# design.net
KiCad netlist of a schematic drawn in Altium Designer
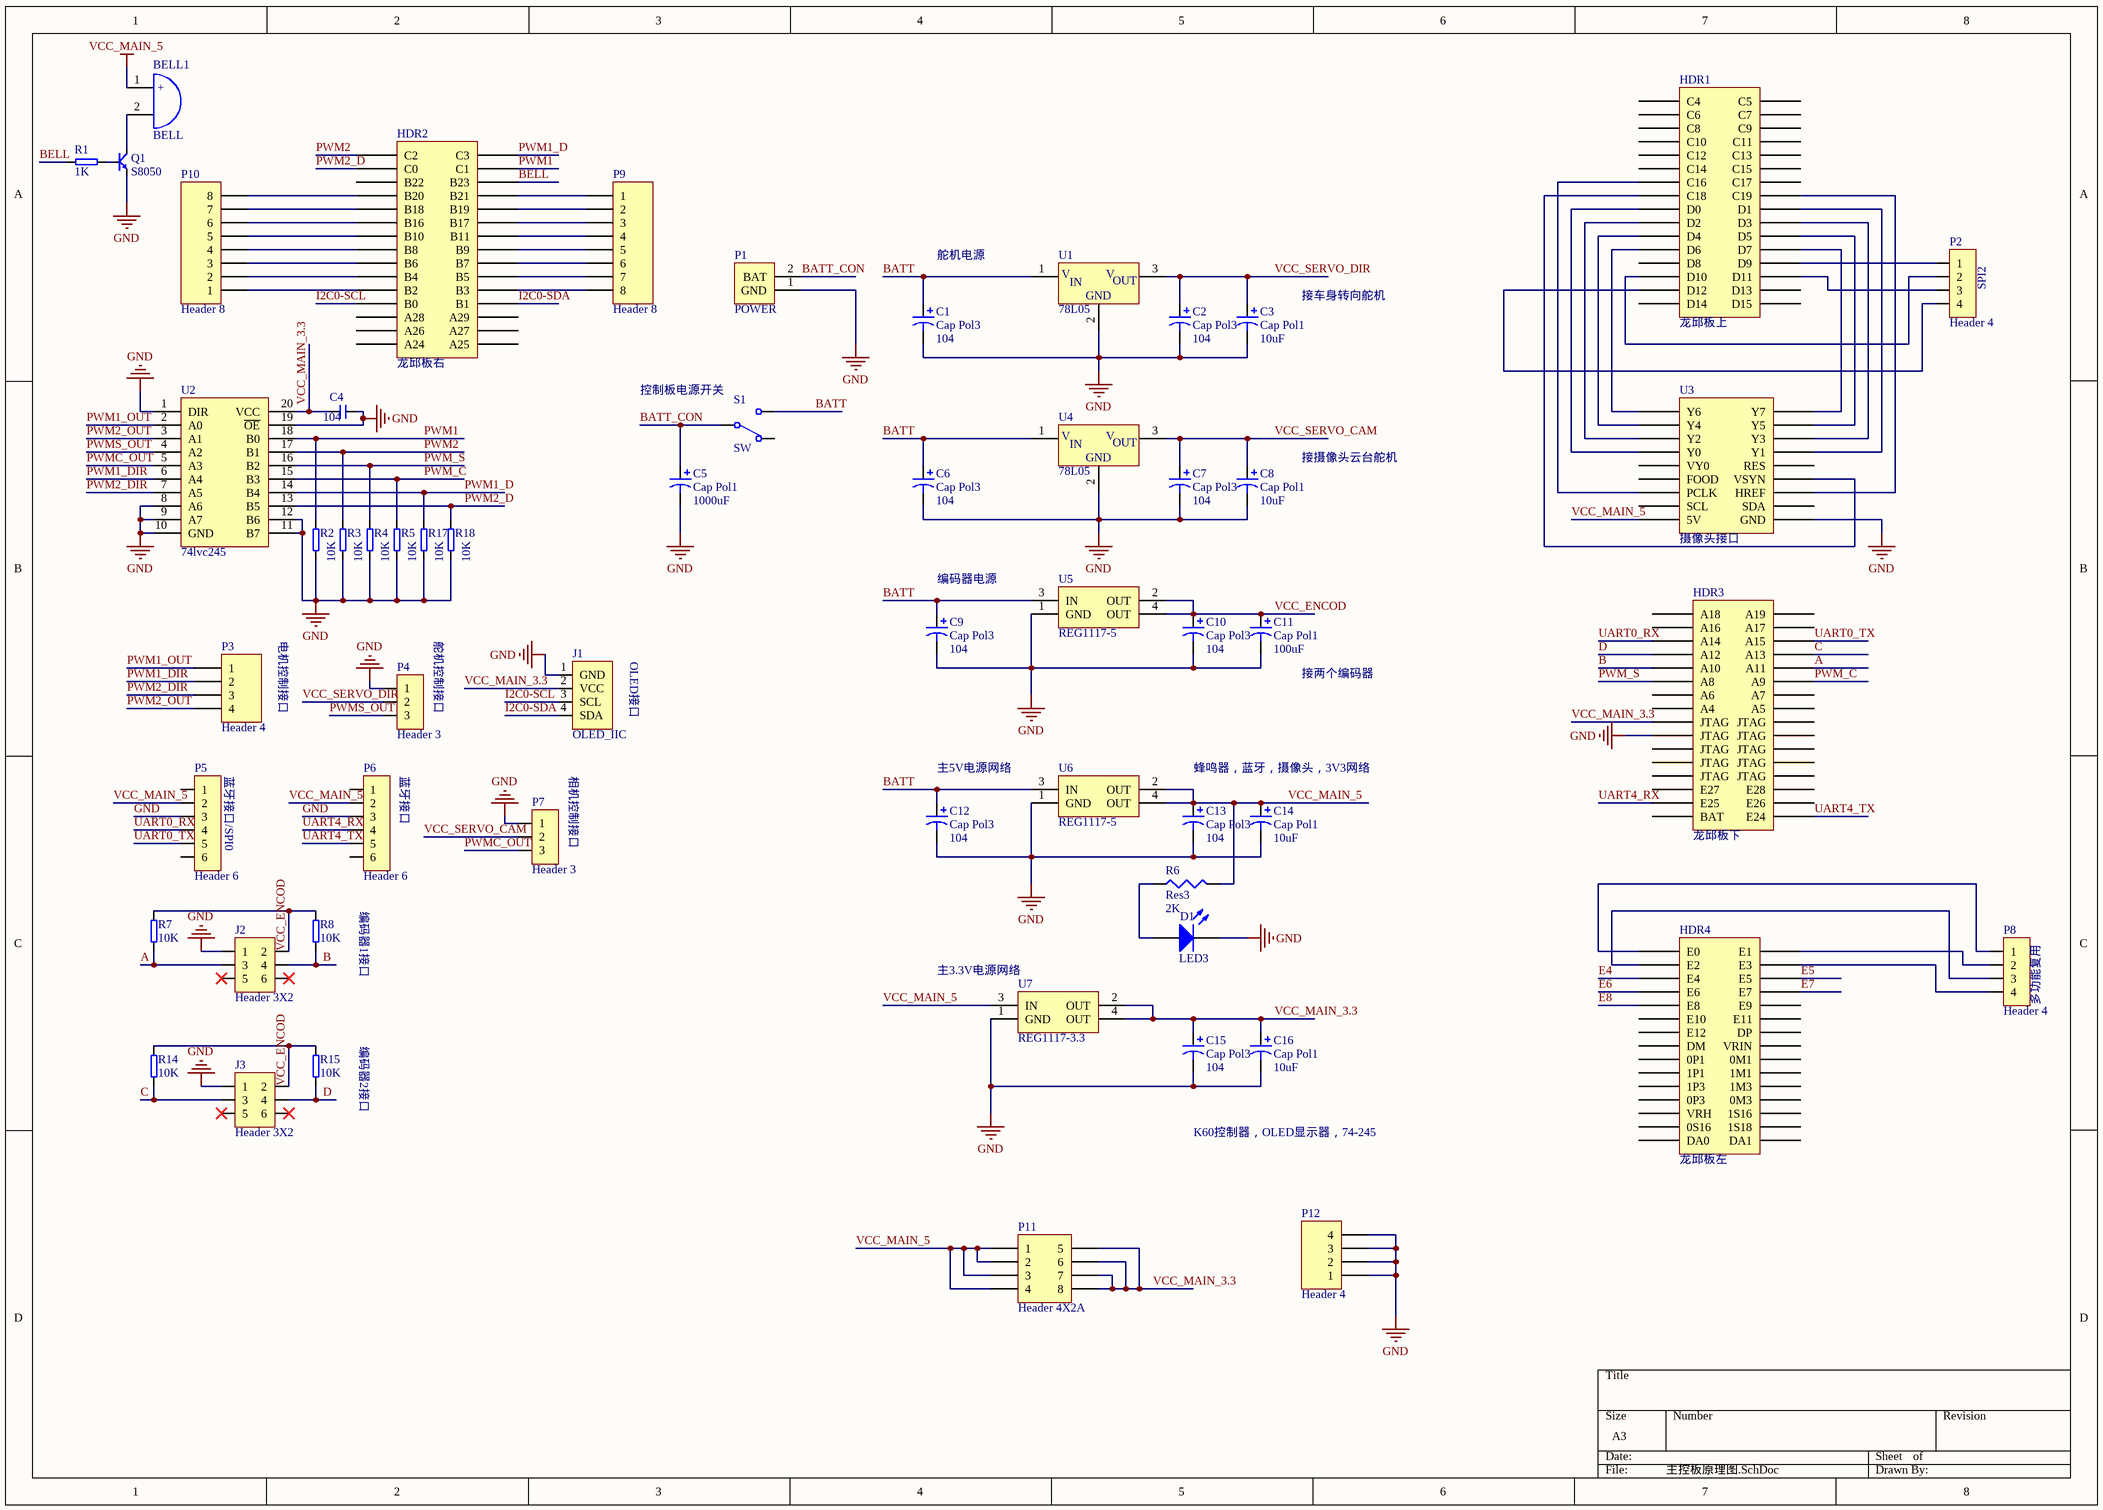
[diagram p0: 主控板原理图.SchDoc]

(export (version "E")
  (design (tool "Eeschema 10.0.6"))
  (components
    (comp (ref "BELL1")
      (value "BELL")
      (footprint "BUZZER")
      (libsource (lib "2017elec_Library") (part "BELL"))
    )
    (comp (ref "C1")
      (value "Cap Pol3")
      (footprint "C0805")
      (description "Polarized Capacitor (Surface Mount)")
      (fields (field (name "ALTIUM_VALUE") "104") (field (name "PUBLISHER") "Altium Limited"))
      (libsource (lib "Miscellaneous Devices") (part "Cap Pol3"))
    )
    (comp (ref "C2")
      (value "Cap Pol3")
      (footprint "C0805")
      (description "Polarized Capacitor (Surface Mount)")
      (fields (field (name "ALTIUM_VALUE") "104") (field (name "PUBLISHER") "Altium Limited"))
      (libsource (lib "Miscellaneous Devices") (part "Cap Pol3"))
    )
    (comp (ref "C3")
      (value "Cap Pol1")
      (footprint "3216-CAP-TA")
      (description "Polarized Capacitor (Radial)")
      (fields (field (name "ALTIUM_VALUE") "10uF") (field (name "PUBLISHER") "Altium Limited"))
      (libsource (lib "Miscellaneous Devices") (part "Cap Pol1"))
    )
    (comp (ref "C4")
      (value "104")
      (footprint "0603-CAP")
      (libsource (lib "2017elec_Library") (part "CAP_0603"))
    )
    (comp (ref "C5")
      (value "Cap Pol1")
      (footprint "CAPP")
      (description "Polarized Capacitor (Radial)")
      (fields (field (name "ALTIUM_VALUE") "1000uF") (field (name "PUBLISHER") "Altium Limited"))
      (libsource (lib "Miscellaneous Devices") (part "Cap Pol1"))
    )
    (comp (ref "C6")
      (value "Cap Pol3")
      (footprint "C0805")
      (description "Polarized Capacitor (Surface Mount)")
      (fields (field (name "ALTIUM_VALUE") "104") (field (name "PUBLISHER") "Altium Limited"))
      (libsource (lib "Miscellaneous Devices") (part "Cap Pol3"))
    )
    (comp (ref "C7")
      (value "Cap Pol3")
      (footprint "C0805")
      (description "Polarized Capacitor (Surface Mount)")
      (fields (field (name "ALTIUM_VALUE") "104") (field (name "PUBLISHER") "Altium Limited"))
      (libsource (lib "Miscellaneous Devices") (part "Cap Pol3"))
    )
    (comp (ref "C8")
      (value "Cap Pol1")
      (footprint "3216-CAP-TA")
      (description "Polarized Capacitor (Radial)")
      (fields (field (name "ALTIUM_VALUE") "10uF") (field (name "PUBLISHER") "Altium Limited"))
      (libsource (lib "Miscellaneous Devices") (part "Cap Pol1"))
    )
    (comp (ref "C9")
      (value "Cap Pol3")
      (footprint "C0805")
      (description "Polarized Capacitor (Surface Mount)")
      (fields (field (name "ALTIUM_VALUE") "104") (field (name "PUBLISHER") "Altium Limited"))
      (libsource (lib "Miscellaneous Devices") (part "Cap Pol3"))
    )
    (comp (ref "C10")
      (value "Cap Pol3")
      (footprint "C0805")
      (description "Polarized Capacitor (Surface Mount)")
      (fields (field (name "ALTIUM_VALUE") "104") (field (name "PUBLISHER") "Altium Limited"))
      (libsource (lib "Miscellaneous Devices") (part "Cap Pol3"))
    )
    (comp (ref "C11")
      (value "Cap Pol1")
      (footprint "RB.1/.2")
      (description "Polarized Capacitor (Radial)")
      (fields (field (name "ALTIUM_VALUE") "100uF") (field (name "PUBLISHER") "Altium Limited"))
      (libsource (lib "Miscellaneous Devices") (part "Cap Pol1"))
    )
    (comp (ref "C12")
      (value "Cap Pol3")
      (footprint "C0805")
      (description "Polarized Capacitor (Surface Mount)")
      (fields (field (name "ALTIUM_VALUE") "104") (field (name "PUBLISHER") "Altium Limited"))
      (libsource (lib "Miscellaneous Devices") (part "Cap Pol3"))
    )
    (comp (ref "C13")
      (value "Cap Pol3")
      (footprint "C0805")
      (description "Polarized Capacitor (Surface Mount)")
      (fields (field (name "ALTIUM_VALUE") "104") (field (name "PUBLISHER") "Altium Limited"))
      (libsource (lib "Miscellaneous Devices") (part "Cap Pol3"))
    )
    (comp (ref "C14")
      (value "Cap Pol1")
      (footprint "3216-CAP-TA")
      (description "Polarized Capacitor (Radial)")
      (fields (field (name "ALTIUM_VALUE") "10uF") (field (name "PUBLISHER") "Altium Limited"))
      (libsource (lib "Miscellaneous Devices") (part "Cap Pol1"))
    )
    (comp (ref "C15")
      (value "Cap Pol3")
      (footprint "C0805")
      (description "Polarized Capacitor (Surface Mount)")
      (fields (field (name "ALTIUM_VALUE") "104") (field (name "PUBLISHER") "Altium Limited"))
      (libsource (lib "Miscellaneous Devices") (part "Cap Pol3"))
    )
    (comp (ref "C16")
      (value "Cap Pol1")
      (footprint "3216-CAP-TA")
      (description "Polarized Capacitor (Radial)")
      (fields (field (name "ALTIUM_VALUE") "10uF") (field (name "PUBLISHER") "Altium Limited"))
      (libsource (lib "Miscellaneous Devices") (part "Cap Pol1"))
    )
    (comp (ref "D1")
      (value "LED3")
      (footprint "3.5X2.8X1.9")
      (description "Typical BLUE SiC LED")
      (fields (field (name "PUBLISHER") "Altium Limited"))
      (libsource (lib "Miscellaneous Devices") (part "LED3"))
    )
    (comp (ref "HDR1") (value "龙邱板上") (footprint "HDR2X16_CEN") (libsource (lib "龙邱板插件") (part "龙邱板上")))
    (comp (ref "HDR2") (value "龙邱板右") (footprint "HDR2X15_CEN") (libsource (lib "龙邱板插件") (part "龙邱板右")))
    (comp (ref "HDR3") (value "龙邱板下") (footprint "HDR2X16_CEN") (libsource (lib "龙邱板插件") (part "龙邱板下")))
    (comp (ref "HDR4") (value "龙邱板左") (footprint "HDR2X15_CEN") (libsource (lib "龙邱板插件") (part "龙邱板左")))
    (comp (ref "J1")
      (value "OLED_IIC")
      (footprint "Header 4")
      (libsource (lib "2017elec_Library") (part "OLED_IIC"))
    )
    (comp (ref "J2")
      (value "Header 3X2")
      (footprint "IDC3*2")
      (libsource (lib "2017elec_Library") (part "Header 3X2"))
    )
    (comp (ref "J3")
      (value "Header 3X2")
      (footprint "IDC3*2")
      (libsource (lib "2017elec_Library") (part "Header 3X2"))
    )
    (comp (ref "P1") (value "POWER") (footprint "POWER") (libsource (lib "2017elec_Library") (part "POWER")))
    (comp (ref "P2")
      (value "Header 4")
      (footprint "Header 4")
      (libsource (lib "2017_elec主板") (part "Header 4"))
    )
    (comp (ref "P3")
      (value "Header 4")
      (footprint "HDR1X4")
      (description "Header, 4-Pin")
      (fields (field (name "PUBLISHER") "Altium Limited"))
      (libsource (lib "Miscellaneous Connectors") (part "Header 4"))
    )
    (comp (ref "P4")
      (value "Header 3")
      (footprint "Header 3")
      (libsource (lib "2017elec_Library") (part "Header 3"))
    )
    (comp (ref "P5")
      (value "Header 6")
      (footprint "Header 6")
      (libsource (lib "2017elec_Library") (part "Header 6"))
    )
    (comp (ref "P6")
      (value "Header 6")
      (footprint "Header 6")
      (libsource (lib "2017elec_Library") (part "Header 6"))
    )
    (comp (ref "P7")
      (value "Header 3")
      (footprint "Header 3")
      (libsource (lib "2017elec_Library") (part "Header 3"))
    )
    (comp (ref "P8")
      (value "Header 4")
      (footprint "Header 4")
      (libsource (lib "2017_elec主板") (part "Header 4"))
    )
    (comp (ref "P9")
      (value "Header 8")
      (footprint "HDR1X8")
      (description "Header, 8-Pin")
      (fields (field (name "PUBLISHER") "Altium Limited"))
      (libsource (lib "Miscellaneous Connectors") (part "Header 8"))
    )
    (comp (ref "P10")
      (value "Header 8")
      (footprint "HDR1X8")
      (description "Header, 8-Pin")
      (fields (field (name "PUBLISHER") "Altium Limited"))
      (libsource (lib "") (part "Header 8_1"))
    )
    (comp (ref "P11")
      (value "Header 4X2A")
      (footprint "HDR2X4_CEN")
      (description "Header, 4-Pin, Dual row")
      (fields (field (name "PUBLISHER") "Altium Limited"))
      (libsource (lib "Miscellaneous Connectors") (part "Header 4X2A"))
    )
    (comp (ref "P12")
      (value "Header 4")
      (footprint "HDR1X4")
      (description "Header, 4-Pin")
      (fields (field (name "PUBLISHER") "Altium Limited"))
      (libsource (lib "") (part "Header 4_1"))
    )
    (comp (ref "Q1") (value "S8050") (footprint "8050") (libsource (lib "2017elec_Library") (part "NPN")))
    (comp (ref "R1")
      (value "1K")
      (footprint "0603-RES")
      (libsource (lib "2017elec_Library") (part "RES_0603"))
    )
    (comp (ref "R2")
      (value "10K")
      (footprint "0603-RES")
      (libsource (lib "2017elec_Library") (part "RES_0603"))
    )
    (comp (ref "R3")
      (value "10K")
      (footprint "0603-RES")
      (libsource (lib "2017elec_Library") (part "RES_0603"))
    )
    (comp (ref "R4")
      (value "10K")
      (footprint "0603-RES")
      (libsource (lib "2017elec_Library") (part "RES_0603"))
    )
    (comp (ref "R5")
      (value "10K")
      (footprint "0603-RES")
      (libsource (lib "2017elec_Library") (part "RES_0603"))
    )
    (comp (ref "R6")
      (value "Res3")
      (footprint "J1-0603")
      (description "Resistor")
      (fields (field (name "ALTIUM_VALUE") "2K") (field (name "PUBLISHER") "Altium Limited"))
      (libsource (lib "Miscellaneous Devices") (part "Res3"))
    )
    (comp (ref "R7")
      (value "10K")
      (footprint "0603-RES")
      (libsource (lib "2017elec_Library") (part "RES_0603"))
    )
    (comp (ref "R8")
      (value "10K")
      (footprint "0603-RES")
      (libsource (lib "2017elec_Library") (part "RES_0603"))
    )
    (comp (ref "R14")
      (value "10K")
      (footprint "0603-RES")
      (libsource (lib "2017elec_Library") (part "RES_0603"))
    )
    (comp (ref "R15")
      (value "10K")
      (footprint "0603-RES")
      (libsource (lib "2017elec_Library") (part "RES_0603"))
    )
    (comp (ref "R17")
      (value "10K")
      (footprint "0603-RES")
      (libsource (lib "2017elec_Library") (part "RES_0603"))
    )
    (comp (ref "R18")
      (value "10K")
      (footprint "0603-RES")
      (libsource (lib "2017elec_Library") (part "RES_0603"))
    )
    (comp (ref "S1") (value "SW") (footprint "SW") (libsource (lib "My K60") (part "SW")))
    (comp (ref "U1")
      (value "78L05")
      (footprint "78XX")
      (description "3-Terminal Positive Voltage Regulator")
      (libsource (lib "78稳压块") (part "78L05"))
    )
    (comp (ref "U2")
      (value "74lvc245")
      (footprint "74lvc245 TSSOP20")
      (libsource (lib "2017elec_Library") (part "74lvc245"))
    )
    (comp (ref "U3") (value "摄像头接口") (footprint "HDR2X9_CEN") (libsource (lib "龙邱板插件") (part "摄像头接口")))
    (comp (ref "U4")
      (value "78L05")
      (footprint "78XX")
      (description "3-Terminal Positive Voltage Regulator")
      (libsource (lib "78稳压块") (part "78L05"))
    )
    (comp (ref "U5")
      (value "REG1117-5")
      (footprint "ZZ311")
      (description "800mA and 1A Low Dropout Positive Regulator 2.85V, 3.3V, 5V, and Adjustable")
      (fields (field (name "PUBLISHER") "Altium Limited"))
      (libsource (lib "BB Power Mgt Voltage Regulator") (part "REG1117-5"))
    )
    (comp (ref "U6")
      (value "REG1117-5")
      (footprint "ZZ311")
      (description "800mA and 1A Low Dropout Positive Regulator 2.85V, 3.3V, 5V, and Adjustable")
      (fields (field (name "PUBLISHER") "Altium Limited"))
      (libsource (lib "BB Power Mgt Voltage Regulator") (part "REG1117-5"))
    )
    (comp (ref "U7")
      (value "REG1117-3.3")
      (footprint "ZZ311")
      (description "800mA and 1A Low Dropout Positive Regulator 2.85V, 3.3V, 5V, and Adjustable")
      (fields (field (name "PUBLISHER") "Altium Limited"))
      (libsource (lib "BB Power Mgt Voltage Regulator") (part "REG1117-3.3"))
    )
  )
  (nets
    (net (code "1") (name "/A") (class "Default")
      (node (ref "HDR3") (pin "12") (pinfunction "A11_12") (pintype "passive"))
      (node (ref "J2") (pin "3") (pinfunction "3_3") (pintype "passive"))
      (node (ref "R7") (pin "1") (pinfunction "1_1") (pintype "passive"))
    )
    (net (code "2") (name "/B") (class "Default")
      (node (ref "HDR3") (pin "28") (pinfunction "A10_28") (pintype "passive"))
      (node (ref "J2") (pin "4") (pinfunction "4_4") (pintype "passive"))
      (node (ref "R8") (pin "1") (pinfunction "1_1") (pintype "passive"))
    )
    (net (code "3") (name "/BATT") (class "Default")
      (node (ref "C1") (pin "1") (pinfunction "1_1") (pintype "passive"))
      (node (ref "C12") (pin "1") (pinfunction "1_1") (pintype "passive"))
      (node (ref "C6") (pin "1") (pinfunction "1_1") (pintype "passive"))
      (node (ref "C9") (pin "1") (pinfunction "1_1") (pintype "passive"))
      (node (ref "S1") (pin "3") (pinfunction "3_3") (pintype "passive"))
      (node (ref "U1") (pin "1") (pinfunction "VIN_1") (pintype "passive"))
      (node (ref "U4") (pin "1") (pinfunction "VIN_1") (pintype "passive"))
      (node (ref "U5") (pin "3") (pinfunction "IN_3") (pintype "power_in"))
      (node (ref "U6") (pin "3") (pinfunction "IN_3") (pintype "power_in"))
    )
    (net (code "4") (name "/BATT_CON") (class "Default")
      (node (ref "C5") (pin "1") (pinfunction "1_1") (pintype "passive"))
      (node (ref "P1") (pin "2") (pinfunction "BAT_2") (pintype "passive"))
      (node (ref "S1") (pin "2") (pinfunction "2_2") (pintype "passive"))
    )
    (net (code "5") (name "/BELL") (class "Default")
      (node (ref "HDR2") (pin "18") (pinfunction "B23_18") (pintype "passive"))
      (node (ref "R1") (pin "1") (pinfunction "1_1") (pintype "passive"))
    )
    (net (code "6") (name "/C") (class "Default")
      (node (ref "HDR3") (pin "13") (pinfunction "A13_13") (pintype "passive"))
      (node (ref "J3") (pin "3") (pinfunction "3_3") (pintype "passive"))
      (node (ref "R14") (pin "1") (pinfunction "1_1") (pintype "passive"))
    )
    (net (code "7") (name "/D") (class "Default")
      (node (ref "HDR3") (pin "29") (pinfunction "A12_29") (pintype "passive"))
      (node (ref "J3") (pin "4") (pinfunction "4_4") (pintype "passive"))
      (node (ref "R15") (pin "1") (pinfunction "1_1") (pintype "passive"))
    )
    (net (code "8") (name "/E4") (class "Default")
      (node (ref "HDR4") (pin "3") (pinfunction "E4_3") (pintype "passive"))
    )
    (net (code "9") (name "/E5") (class "Default")
      (node (ref "HDR4") (pin "18") (pinfunction "E5_18") (pintype "passive"))
    )
    (net (code "10") (name "/E6") (class "Default")
      (node (ref "HDR4") (pin "4") (pinfunction "E6_4") (pintype "passive"))
    )
    (net (code "11") (name "/E7") (class "Default")
      (node (ref "HDR4") (pin "19") (pinfunction "E7_19") (pintype "passive"))
    )
    (net (code "12") (name "/E8") (class "Default")
      (node (ref "HDR4") (pin "5") (pinfunction "E8_5") (pintype "passive"))
    )
    (net (code "13") (name "/I2C0-SCL") (class "Default")
      (node (ref "HDR2") (pin "12") (pinfunction "B0_12") (pintype "passive"))
      (node (ref "J1") (pin "3") (pinfunction "SCL_3") (pintype "passive"))
    )
    (net (code "14") (name "/I2C0-SDA") (class "Default")
      (node (ref "HDR2") (pin "27") (pinfunction "B1_27") (pintype "passive"))
      (node (ref "J1") (pin "4") (pinfunction "SDA_4") (pintype "passive"))
    )
    (net (code "15") (name "/PWM1") (class "Default")
      (node (ref "HDR2") (pin "17") (pinfunction "C1_17") (pintype "passive"))
      (node (ref "R2") (pin "2") (pinfunction "2_2") (pintype "passive"))
      (node (ref "U2") (pin "18") (pinfunction "B0_18") (pintype "passive"))
    )
    (net (code "16") (name "/PWM1_D") (class "Default")
      (node (ref "HDR2") (pin "16") (pinfunction "C3_16") (pintype "passive"))
      (node (ref "R17") (pin "2") (pinfunction "2_2") (pintype "passive"))
      (node (ref "U2") (pin "14") (pinfunction "B4_14") (pintype "passive"))
    )
    (net (code "17") (name "/PWM1_DIR") (class "Default")
      (node (ref "P3") (pin "2") (pinfunction "2_2") (pintype "passive"))
      (node (ref "U2") (pin "6") (pinfunction "A4_6") (pintype "passive"))
    )
    (net (code "18") (name "/PWM1_OUT") (class "Default")
      (node (ref "P3") (pin "1") (pinfunction "1_1") (pintype "passive"))
      (node (ref "U2") (pin "2") (pinfunction "A0_2") (pintype "passive"))
    )
    (net (code "19") (name "/PWM2") (class "Default")
      (node (ref "HDR2") (pin "1") (pinfunction "C2_1") (pintype "passive"))
      (node (ref "R3") (pin "2") (pinfunction "2_2") (pintype "passive"))
      (node (ref "U2") (pin "17") (pinfunction "B1_17") (pintype "passive"))
    )
    (net (code "20") (name "/PWM2_D") (class "Default")
      (node (ref "HDR2") (pin "2") (pinfunction "C0_2") (pintype "passive"))
      (node (ref "R18") (pin "2") (pinfunction "2_2") (pintype "passive"))
      (node (ref "U2") (pin "13") (pinfunction "B5_13") (pintype "passive"))
    )
    (net (code "21") (name "/PWM2_DIR") (class "Default")
      (node (ref "P3") (pin "3") (pinfunction "3_3") (pintype "passive"))
      (node (ref "U2") (pin "7") (pinfunction "A5_7") (pintype "passive"))
    )
    (net (code "22") (name "/PWM2_OUT") (class "Default")
      (node (ref "P3") (pin "4") (pinfunction "4_4") (pintype "passive"))
      (node (ref "U2") (pin "3") (pinfunction "A1_3") (pintype "passive"))
    )
    (net (code "23") (name "/PWMC_OUT") (class "Default")
      (node (ref "P7") (pin "3") (pinfunction "3_3") (pintype "passive"))
      (node (ref "U2") (pin "5") (pinfunction "A3_5") (pintype "passive"))
    )
    (net (code "24") (name "/PWMS_OUT") (class "Default")
      (node (ref "P4") (pin "3") (pinfunction "3_3") (pintype "passive"))
      (node (ref "U2") (pin "4") (pinfunction "A2_4") (pintype "passive"))
    )
    (net (code "25") (name "/PWM_C") (class "Default")
      (node (ref "HDR3") (pin "11") (pinfunction "A9_11") (pintype "passive"))
      (node (ref "R5") (pin "2") (pinfunction "2_2") (pintype "passive"))
      (node (ref "U2") (pin "15") (pinfunction "B3_15") (pintype "passive"))
    )
    (net (code "26") (name "/PWM_S") (class "Default")
      (node (ref "HDR3") (pin "27") (pinfunction "A8_27") (pintype "passive"))
      (node (ref "R4") (pin "2") (pinfunction "2_2") (pintype "passive"))
      (node (ref "U2") (pin "16") (pinfunction "B2_16") (pintype "passive"))
    )
    (net (code "27") (name "/UART0_RX") (class "Default")
      (node (ref "HDR3") (pin "30") (pinfunction "A14_30") (pintype "passive"))
      (node (ref "P5") (pin "4") (pinfunction "4_4") (pintype "passive"))
    )
    (net (code "28") (name "/UART0_TX") (class "Default")
      (node (ref "HDR3") (pin "14") (pinfunction "A15_14") (pintype "passive"))
      (node (ref "P5") (pin "5") (pinfunction "5_5") (pintype "passive"))
    )
    (net (code "29") (name "/UART4_RX") (class "Default")
      (node (ref "HDR3") (pin "18") (pinfunction "E25_18") (pintype "passive"))
      (node (ref "P6") (pin "4") (pinfunction "4_4") (pintype "passive"))
    )
    (net (code "30") (name "/UART4_TX") (class "Default")
      (node (ref "HDR3") (pin "1") (pinfunction "E24_1") (pintype "passive"))
      (node (ref "P6") (pin "5") (pinfunction "5_5") (pintype "passive"))
    )
    (net (code "31") (name "/VCC_ENCOD") (class "Default")
      (node (ref "C10") (pin "1") (pinfunction "1_1") (pintype "passive"))
      (node (ref "C11") (pin "1") (pinfunction "1_1") (pintype "passive"))
      (node (ref "J2") (pin "2") (pinfunction "2_2") (pintype "passive"))
      (node (ref "J3") (pin "2") (pinfunction "2_2") (pintype "passive"))
      (node (ref "R14") (pin "2") (pinfunction "2_2") (pintype "passive"))
      (node (ref "R15") (pin "2") (pinfunction "2_2") (pintype "passive"))
      (node (ref "R7") (pin "2") (pinfunction "2_2") (pintype "passive"))
      (node (ref "R8") (pin "2") (pinfunction "2_2") (pintype "passive"))
      (node (ref "U5") (pin "2") (pinfunction "OUT_2") (pintype "power_in"))
      (node (ref "U5") (pin "4") (pinfunction "OUT_4") (pintype "power_in"))
    )
    (net (code "32") (name "/VCC_MAIN_3.3") (class "Default")
      (node (ref "C15") (pin "1") (pinfunction "1_1") (pintype "passive"))
      (node (ref "C16") (pin "1") (pinfunction "1_1") (pintype "passive"))
      (node (ref "C4") (pin "1") (pinfunction "1_1") (pintype "passive"))
      (node (ref "HDR3") (pin "24") (pinfunction "JTAG_24") (pintype "passive"))
      (node (ref "J1") (pin "2") (pinfunction "VCC_2") (pintype "passive"))
      (node (ref "P11") (pin "5") (pinfunction "5_5") (pintype "passive"))
      (node (ref "P11") (pin "6") (pinfunction "6_6") (pintype "passive"))
      (node (ref "P11") (pin "7") (pinfunction "7_7") (pintype "passive"))
      (node (ref "P11") (pin "8") (pinfunction "8_8") (pintype "passive"))
      (node (ref "U2") (pin "20") (pinfunction "VCC_20") (pintype "passive"))
      (node (ref "U7") (pin "2") (pinfunction "OUT_2") (pintype "power_in"))
      (node (ref "U7") (pin "4") (pinfunction "OUT_4") (pintype "power_in"))
    )
    (net (code "33") (name "/VCC_SERVO_CAM") (class "Default")
      (node (ref "C7") (pin "1") (pinfunction "1_1") (pintype "passive"))
      (node (ref "C8") (pin "1") (pinfunction "1_1") (pintype "passive"))
      (node (ref "P7") (pin "2") (pinfunction "2_2") (pintype "passive"))
      (node (ref "U4") (pin "3") (pinfunction "VOUT_3") (pintype "passive"))
    )
    (net (code "34") (name "/VCC_SERVO_DIR") (class "Default")
      (node (ref "C2") (pin "1") (pinfunction "1_1") (pintype "passive"))
      (node (ref "C3") (pin "1") (pinfunction "1_1") (pintype "passive"))
      (node (ref "P4") (pin "2") (pinfunction "2_2") (pintype "passive"))
      (node (ref "U1") (pin "3") (pinfunction "VOUT_3") (pintype "passive"))
    )
    (net (code "35") (name "GND") (class "Default")
      (node (ref "C1") (pin "2") (pinfunction "2_2") (pintype "passive"))
      (node (ref "C10") (pin "2") (pinfunction "2_2") (pintype "passive"))
      (node (ref "C11") (pin "2") (pinfunction "2_2") (pintype "passive"))
      (node (ref "C12") (pin "2") (pinfunction "2_2") (pintype "passive"))
      (node (ref "C13") (pin "2") (pinfunction "2_2") (pintype "passive"))
      (node (ref "C14") (pin "2") (pinfunction "2_2") (pintype "passive"))
      (node (ref "C15") (pin "2") (pinfunction "2_2") (pintype "passive"))
      (node (ref "C16") (pin "2") (pinfunction "2_2") (pintype "passive"))
      (node (ref "C2") (pin "2") (pinfunction "2_2") (pintype "passive"))
      (node (ref "C3") (pin "2") (pinfunction "2_2") (pintype "passive"))
      (node (ref "C4") (pin "2") (pinfunction "2_2") (pintype "passive"))
      (node (ref "C5") (pin "2") (pinfunction "2_2") (pintype "passive"))
      (node (ref "C6") (pin "2") (pinfunction "2_2") (pintype "passive"))
      (node (ref "C7") (pin "2") (pinfunction "2_2") (pintype "passive"))
      (node (ref "C8") (pin "2") (pinfunction "2_2") (pintype "passive"))
      (node (ref "C9") (pin "2") (pinfunction "2_2") (pintype "passive"))
      (node (ref "D1") (pin "2") (pinfunction "K_2") (pintype "passive"))
      (node (ref "HDR3") (pin "23") (pinfunction "JTAG_23") (pintype "passive"))
      (node (ref "J1") (pin "1") (pinfunction "GND_1") (pintype "passive"))
      (node (ref "J2") (pin "1") (pinfunction "1_1") (pintype "passive"))
      (node (ref "J3") (pin "1") (pinfunction "1_1") (pintype "passive"))
      (node (ref "P1") (pin "1") (pinfunction "GND_1") (pintype "passive"))
      (node (ref "P12") (pin "1") (pinfunction "1_1") (pintype "passive"))
      (node (ref "P12") (pin "2") (pinfunction "2_2") (pintype "passive"))
      (node (ref "P12") (pin "3") (pinfunction "3_3") (pintype "passive"))
      (node (ref "P12") (pin "4") (pinfunction "4_4") (pintype "passive"))
      (node (ref "P4") (pin "1") (pinfunction "1_1") (pintype "passive"))
      (node (ref "P5") (pin "3") (pinfunction "3_3") (pintype "passive"))
      (node (ref "P6") (pin "3") (pinfunction "3_3") (pintype "passive"))
      (node (ref "P7") (pin "1") (pinfunction "1_1") (pintype "passive"))
      (node (ref "Q1") (pin "2") (pinfunction "2_2") (pintype "passive"))
      (node (ref "R17") (pin "1") (pinfunction "1_1") (pintype "passive"))
      (node (ref "R18") (pin "1") (pinfunction "1_1") (pintype "passive"))
      (node (ref "R2") (pin "1") (pinfunction "1_1") (pintype "passive"))
      (node (ref "R3") (pin "1") (pinfunction "1_1") (pintype "passive"))
      (node (ref "R4") (pin "1") (pinfunction "1_1") (pintype "passive"))
      (node (ref "R5") (pin "1") (pinfunction "1_1") (pintype "passive"))
      (node (ref "U1") (pin "2") (pinfunction "GND_2") (pintype "passive"))
      (node (ref "U2") (pin "1") (pinfunction "DIR_1") (pintype "passive"))
      (node (ref "U2") (pin "10") (pinfunction "GND_10") (pintype "passive"))
      (node (ref "U2") (pin "11") (pinfunction "B7_11") (pintype "passive"))
      (node (ref "U2") (pin "12") (pinfunction "B6_12") (pintype "passive"))
      (node (ref "U2") (pin "19") (pinfunction "~{OE}_19") (pintype "passive"))
      (node (ref "U2") (pin "8") (pinfunction "A6_8") (pintype "passive"))
      (node (ref "U2") (pin "9") (pinfunction "A7_9") (pintype "passive"))
      (node (ref "U3") (pin "1") (pinfunction "GND_1") (pintype "passive"))
      (node (ref "U4") (pin "2") (pinfunction "GND_2") (pintype "passive"))
      (node (ref "U5") (pin "1") (pinfunction "GND_1") (pintype "power_in"))
      (node (ref "U6") (pin "1") (pinfunction "GND_1") (pintype "power_in"))
      (node (ref "U7") (pin "1") (pinfunction "GND_1") (pintype "power_in"))
    )
    (net (code "36") (name "Net-(BELL1-Pad2)") (class "Default")
      (node (ref "BELL1") (pin "2") (pinfunction "2_2") (pintype "passive"))
      (node (ref "Q1") (pin "3") (pinfunction "3_3") (pintype "passive"))
    )
    (net (code "37") (name "Net-(D1-A)") (class "Default")
      (node (ref "D1") (pin "1") (pinfunction "A_1") (pintype "passive"))
      (node (ref "R6") (pin "1") (pinfunction "1_1") (pintype "passive"))
    )
    (net (code "38") (name "Net-(HDR1-C16)") (class "Default")
      (node (ref "HDR1") (pin "26") (pinfunction "C16_26") (pintype "passive"))
      (node (ref "U3") (pin "12") (pinfunction "PCLK_12") (pintype "passive"))
    )
    (net (code "39") (name "Net-(HDR1-C18)") (class "Default")
      (node (ref "HDR1") (pin "25") (pinfunction "C18_25") (pintype "passive"))
      (node (ref "U3") (pin "4") (pinfunction "VSYN_4") (pintype "passive"))
    )
    (net (code "40") (name "Net-(HDR1-C19)") (class "Default")
      (node (ref "HDR1") (pin "9") (pinfunction "C19_9") (pintype "passive"))
      (node (ref "U3") (pin "3") (pinfunction "HREF_3") (pintype "passive"))
    )
    (net (code "41") (name "Net-(HDR1-D0)") (class "Default")
      (node (ref "HDR1") (pin "24") (pinfunction "D0_24") (pintype "passive"))
      (node (ref "U3") (pin "15") (pinfunction "Y0_15") (pintype "passive"))
    )
    (net (code "42") (name "Net-(HDR1-D1)") (class "Default")
      (node (ref "HDR1") (pin "8") (pinfunction "D1_8") (pintype "passive"))
      (node (ref "U3") (pin "6") (pinfunction "Y1_6") (pintype "passive"))
    )
    (net (code "43") (name "Net-(HDR1-D2)") (class "Default")
      (node (ref "HDR1") (pin "23") (pinfunction "D2_23") (pintype "passive"))
      (node (ref "U3") (pin "16") (pinfunction "Y2_16") (pintype "passive"))
    )
    (net (code "44") (name "Net-(HDR1-D3)") (class "Default")
      (node (ref "HDR1") (pin "7") (pinfunction "D3_7") (pintype "passive"))
      (node (ref "U3") (pin "7") (pinfunction "Y3_7") (pintype "passive"))
    )
    (net (code "45") (name "Net-(HDR1-D4)") (class "Default")
      (node (ref "HDR1") (pin "22") (pinfunction "D4_22") (pintype "passive"))
      (node (ref "U3") (pin "17") (pinfunction "Y4_17") (pintype "passive"))
    )
    (net (code "46") (name "Net-(HDR1-D5)") (class "Default")
      (node (ref "HDR1") (pin "6") (pinfunction "D5_6") (pintype "passive"))
      (node (ref "U3") (pin "8") (pinfunction "Y5_8") (pintype "passive"))
    )
    (net (code "47") (name "Net-(HDR1-D6)") (class "Default")
      (node (ref "HDR1") (pin "21") (pinfunction "D6_21") (pintype "passive"))
      (node (ref "U3") (pin "18") (pinfunction "Y6_18") (pintype "passive"))
    )
    (net (code "48") (name "Net-(HDR1-D7)") (class "Default")
      (node (ref "HDR1") (pin "5") (pinfunction "D7_5") (pintype "passive"))
      (node (ref "U3") (pin "9") (pinfunction "Y7_9") (pintype "passive"))
    )
    (net (code "49") (name "Net-(HDR1-D9)") (class "Default")
      (node (ref "HDR1") (pin "4") (pinfunction "D9_4") (pintype "passive"))
      (node (ref "P2") (pin "1") (pinfunction "1_1") (pintype "passive"))
    )
    (net (code "50") (name "Net-(HDR1-D10)") (class "Default")
      (node (ref "HDR1") (pin "19") (pinfunction "D10_19") (pintype "passive"))
      (node (ref "P2") (pin "2") (pinfunction "2_2") (pintype "passive"))
    )
    (net (code "51") (name "Net-(HDR1-D11)") (class "Default")
      (node (ref "HDR1") (pin "3") (pinfunction "D11_3") (pintype "passive"))
      (node (ref "P2") (pin "3") (pinfunction "3_3") (pintype "passive"))
    )
    (net (code "52") (name "Net-(HDR1-D12)") (class "Default")
      (node (ref "HDR1") (pin "18") (pinfunction "D12_18") (pintype "passive"))
      (node (ref "P2") (pin "4") (pinfunction "4_4") (pintype "passive"))
    )
    (net (code "53") (name "Net-(HDR2-B2)") (class "Default")
      (node (ref "HDR2") (pin "11") (pinfunction "B2_11") (pintype "passive"))
      (node (ref "P10") (pin "1") (pinfunction "1_1") (pintype "passive"))
    )
    (net (code "54") (name "Net-(HDR2-B3)") (class "Default")
      (node (ref "HDR2") (pin "26") (pinfunction "B3_26") (pintype "passive"))
      (node (ref "P9") (pin "8") (pinfunction "8_8") (pintype "passive"))
    )
    (net (code "55") (name "Net-(HDR2-B4)") (class "Default")
      (node (ref "HDR2") (pin "10") (pinfunction "B4_10") (pintype "passive"))
      (node (ref "P10") (pin "2") (pinfunction "2_2") (pintype "passive"))
    )
    (net (code "56") (name "Net-(HDR2-B5)") (class "Default")
      (node (ref "HDR2") (pin "25") (pinfunction "B5_25") (pintype "passive"))
      (node (ref "P9") (pin "7") (pinfunction "7_7") (pintype "passive"))
    )
    (net (code "57") (name "Net-(HDR2-B6)") (class "Default")
      (node (ref "HDR2") (pin "9") (pinfunction "B6_9") (pintype "passive"))
      (node (ref "P10") (pin "3") (pinfunction "3_3") (pintype "passive"))
    )
    (net (code "58") (name "Net-(HDR2-B7)") (class "Default")
      (node (ref "HDR2") (pin "24") (pinfunction "B7_24") (pintype "passive"))
      (node (ref "P9") (pin "6") (pinfunction "6_6") (pintype "passive"))
    )
    (net (code "59") (name "Net-(HDR2-B8)") (class "Default")
      (node (ref "HDR2") (pin "8") (pinfunction "B8_8") (pintype "passive"))
      (node (ref "P10") (pin "4") (pinfunction "4_4") (pintype "passive"))
    )
    (net (code "60") (name "Net-(HDR2-B9)") (class "Default")
      (node (ref "HDR2") (pin "23") (pinfunction "B9_23") (pintype "passive"))
      (node (ref "P9") (pin "5") (pinfunction "5_5") (pintype "passive"))
    )
    (net (code "61") (name "Net-(HDR2-B10)") (class "Default")
      (node (ref "HDR2") (pin "7") (pinfunction "B10_7") (pintype "passive"))
      (node (ref "P10") (pin "5") (pinfunction "5_5") (pintype "passive"))
    )
    (net (code "62") (name "Net-(HDR2-B11)") (class "Default")
      (node (ref "HDR2") (pin "22") (pinfunction "B11_22") (pintype "passive"))
      (node (ref "P9") (pin "4") (pinfunction "4_4") (pintype "passive"))
    )
    (net (code "63") (name "Net-(HDR2-B16)") (class "Default")
      (node (ref "HDR2") (pin "6") (pinfunction "B16_6") (pintype "passive"))
      (node (ref "P10") (pin "6") (pinfunction "6_6") (pintype "passive"))
    )
    (net (code "64") (name "Net-(HDR2-B17)") (class "Default")
      (node (ref "HDR2") (pin "21") (pinfunction "B17_21") (pintype "passive"))
      (node (ref "P9") (pin "3") (pinfunction "3_3") (pintype "passive"))
    )
    (net (code "65") (name "Net-(HDR2-B18)") (class "Default")
      (node (ref "HDR2") (pin "5") (pinfunction "B18_5") (pintype "passive"))
      (node (ref "P10") (pin "7") (pinfunction "7_7") (pintype "passive"))
    )
    (net (code "66") (name "Net-(HDR2-B19)") (class "Default")
      (node (ref "HDR2") (pin "20") (pinfunction "B19_20") (pintype "passive"))
      (node (ref "P9") (pin "2") (pinfunction "2_2") (pintype "passive"))
    )
    (net (code "67") (name "Net-(HDR2-B20)") (class "Default")
      (node (ref "HDR2") (pin "4") (pinfunction "B20_4") (pintype "passive"))
      (node (ref "P10") (pin "8") (pinfunction "8_8") (pintype "passive"))
    )
    (net (code "68") (name "Net-(HDR2-B21)") (class "Default")
      (node (ref "HDR2") (pin "19") (pinfunction "B21_19") (pintype "passive"))
      (node (ref "P9") (pin "1") (pinfunction "1_1") (pintype "passive"))
    )
    (net (code "69") (name "Net-(HDR4-E0)") (class "Default")
      (node (ref "HDR4") (pin "1") (pinfunction "E0_1") (pintype "passive"))
      (node (ref "P8") (pin "1") (pinfunction "1_1") (pintype "passive"))
    )
    (net (code "70") (name "Net-(HDR4-E1)") (class "Default")
      (node (ref "HDR4") (pin "16") (pinfunction "E1_16") (pintype "passive"))
      (node (ref "P8") (pin "2") (pinfunction "2_2") (pintype "passive"))
    )
    (net (code "71") (name "Net-(HDR4-E2)") (class "Default")
      (node (ref "HDR4") (pin "2") (pinfunction "E2_2") (pintype "passive"))
      (node (ref "P8") (pin "3") (pinfunction "3_3") (pintype "passive"))
    )
    (net (code "72") (name "Net-(HDR4-E3)") (class "Default")
      (node (ref "HDR4") (pin "17") (pinfunction "E3_17") (pintype "passive"))
      (node (ref "P8") (pin "4") (pinfunction "4_4") (pintype "passive"))
    )
    (net (code "73") (name "Net-(Q1-Pad1)") (class "Default")
      (node (ref "Q1") (pin "1") (pinfunction "1_1") (pintype "passive"))
      (node (ref "R1") (pin "2") (pinfunction "2_2") (pintype "passive"))
    )
    (net (code "74") (name "VCC_MAIN_5") (class "Default")
      (node (ref "BELL1") (pin "1") (pinfunction "+_1") (pintype "passive"))
      (node (ref "C13") (pin "1") (pinfunction "1_1") (pintype "passive"))
      (node (ref "C14") (pin "1") (pinfunction "1_1") (pintype "passive"))
      (node (ref "P11") (pin "1") (pinfunction "1_1") (pintype "passive"))
      (node (ref "P11") (pin "2") (pinfunction "2_2") (pintype "passive"))
      (node (ref "P11") (pin "3") (pinfunction "3_3") (pintype "passive"))
      (node (ref "P11") (pin "4") (pinfunction "4_4") (pintype "passive"))
      (node (ref "P5") (pin "2") (pinfunction "2_2") (pintype "passive"))
      (node (ref "P6") (pin "2") (pinfunction "2_2") (pintype "passive"))
      (node (ref "R6") (pin "2") (pinfunction "2_2") (pintype "passive"))
      (node (ref "U3") (pin "10") (pinfunction "5V_10") (pintype "passive"))
      (node (ref "U6") (pin "2") (pinfunction "OUT_2") (pintype "power_in"))
      (node (ref "U6") (pin "4") (pinfunction "OUT_4") (pintype "power_in"))
      (node (ref "U7") (pin "3") (pinfunction "IN_3") (pintype "power_in"))
    )
    (net (code "75") (name "unconnected-(HDR1-C4-Pad32)") (class "Default")
      (node (ref "HDR1") (pin "32") (pinfunction "C4_32") (pintype "passive"))
    )
    (net (code "76") (name "unconnected-(HDR1-C5-Pad16)") (class "Default")
      (node (ref "HDR1") (pin "16") (pinfunction "C5_16") (pintype "passive"))
    )
    (net (code "77") (name "unconnected-(HDR1-C6-Pad31)") (class "Default")
      (node (ref "HDR1") (pin "31") (pinfunction "C6_31") (pintype "passive"))
    )
    (net (code "78") (name "unconnected-(HDR1-C7-Pad15)") (class "Default")
      (node (ref "HDR1") (pin "15") (pinfunction "C7_15") (pintype "passive"))
    )
    (net (code "79") (name "unconnected-(HDR1-C8-Pad30)") (class "Default")
      (node (ref "HDR1") (pin "30") (pinfunction "C8_30") (pintype "passive"))
    )
    (net (code "80") (name "unconnected-(HDR1-C9-Pad14)") (class "Default")
      (node (ref "HDR1") (pin "14") (pinfunction "C9_14") (pintype "passive"))
    )
    (net (code "81") (name "unconnected-(HDR1-C10-Pad29)") (class "Default")
      (node (ref "HDR1") (pin "29") (pinfunction "C10_29") (pintype "passive"))
    )
    (net (code "82") (name "unconnected-(HDR1-C11-Pad13)") (class "Default")
      (node (ref "HDR1") (pin "13") (pinfunction "C11_13") (pintype "passive"))
    )
    (net (code "83") (name "unconnected-(HDR1-C12-Pad28)") (class "Default")
      (node (ref "HDR1") (pin "28") (pinfunction "C12_28") (pintype "passive"))
    )
    (net (code "84") (name "unconnected-(HDR1-C13-Pad12)") (class "Default")
      (node (ref "HDR1") (pin "12") (pinfunction "C13_12") (pintype "passive"))
    )
    (net (code "85") (name "unconnected-(HDR1-C14-Pad27)") (class "Default")
      (node (ref "HDR1") (pin "27") (pinfunction "C14_27") (pintype "passive"))
    )
    (net (code "86") (name "unconnected-(HDR1-C15-Pad11)") (class "Default")
      (node (ref "HDR1") (pin "11") (pinfunction "C15_11") (pintype "passive"))
    )
    (net (code "87") (name "unconnected-(HDR1-C17-Pad10)") (class "Default")
      (node (ref "HDR1") (pin "10") (pinfunction "C17_10") (pintype "passive"))
    )
    (net (code "88") (name "unconnected-(HDR1-D8-Pad20)") (class "Default")
      (node (ref "HDR1") (pin "20") (pinfunction "D8_20") (pintype "passive"))
    )
    (net (code "89") (name "unconnected-(HDR1-D13-Pad2)") (class "Default")
      (node (ref "HDR1") (pin "2") (pinfunction "D13_2") (pintype "passive"))
    )
    (net (code "90") (name "unconnected-(HDR1-D14-Pad17)") (class "Default")
      (node (ref "HDR1") (pin "17") (pinfunction "D14_17") (pintype "passive"))
    )
    (net (code "91") (name "unconnected-(HDR1-D15-Pad1)") (class "Default")
      (node (ref "HDR1") (pin "1") (pinfunction "D15_1") (pintype "passive"))
    )
    (net (code "92") (name "unconnected-(HDR2-A24-Pad15)") (class "Default")
      (node (ref "HDR2") (pin "15") (pinfunction "A24_15") (pintype "passive"))
    )
    (net (code "93") (name "unconnected-(HDR2-A25-Pad30)") (class "Default")
      (node (ref "HDR2") (pin "30") (pinfunction "A25_30") (pintype "passive"))
    )
    (net (code "94") (name "unconnected-(HDR2-A26-Pad14)") (class "Default")
      (node (ref "HDR2") (pin "14") (pinfunction "A26_14") (pintype "passive"))
    )
    (net (code "95") (name "unconnected-(HDR2-A27-Pad29)") (class "Default")
      (node (ref "HDR2") (pin "29") (pinfunction "A27_29") (pintype "passive"))
    )
    (net (code "96") (name "unconnected-(HDR2-A28-Pad13)") (class "Default")
      (node (ref "HDR2") (pin "13") (pinfunction "A28_13") (pintype "passive"))
    )
    (net (code "97") (name "unconnected-(HDR2-A29-Pad28)") (class "Default")
      (node (ref "HDR2") (pin "28") (pinfunction "A29_28") (pintype "passive"))
    )
    (net (code "98") (name "unconnected-(HDR2-B22-Pad3)") (class "Default")
      (node (ref "HDR2") (pin "3") (pinfunction "B22_3") (pintype "passive"))
    )
    (net (code "99") (name "unconnected-(HDR3-A4-Pad25)") (class "Default")
      (node (ref "HDR3") (pin "25") (pinfunction "A4_25") (pintype "passive"))
    )
    (net (code "100") (name "unconnected-(HDR3-A5-Pad9)") (class "Default")
      (node (ref "HDR3") (pin "9") (pinfunction "A5_9") (pintype "passive"))
    )
    (net (code "101") (name "unconnected-(HDR3-A6-Pad26)") (class "Default")
      (node (ref "HDR3") (pin "26") (pinfunction "A6_26") (pintype "passive"))
    )
    (net (code "102") (name "unconnected-(HDR3-A7-Pad10)") (class "Default")
      (node (ref "HDR3") (pin "10") (pinfunction "A7_10") (pintype "passive"))
    )
    (net (code "103") (name "unconnected-(HDR3-A16-Pad31)") (class "Default")
      (node (ref "HDR3") (pin "31") (pinfunction "A16_31") (pintype "passive"))
    )
    (net (code "104") (name "unconnected-(HDR3-A17-Pad15)") (class "Default")
      (node (ref "HDR3") (pin "15") (pinfunction "A17_15") (pintype "passive"))
    )
    (net (code "105") (name "unconnected-(HDR3-A18-Pad32)") (class "Default")
      (node (ref "HDR3") (pin "32") (pinfunction "A18_32") (pintype "passive"))
    )
    (net (code "106") (name "unconnected-(HDR3-A19-Pad16)") (class "Default")
      (node (ref "HDR3") (pin "16") (pinfunction "A19_16") (pintype "passive"))
    )
    (net (code "107") (name "unconnected-(HDR3-BAT-Pad17)") (class "Default")
      (node (ref "HDR3") (pin "17") (pinfunction "BAT_17") (pintype "passive"))
    )
    (net (code "108") (name "unconnected-(HDR3-E26-Pad2)") (class "Default")
      (node (ref "HDR3") (pin "2") (pinfunction "E26_2") (pintype "passive"))
    )
    (net (code "109") (name "unconnected-(HDR3-E27-Pad19)") (class "Default")
      (node (ref "HDR3") (pin "19") (pinfunction "E27_19") (pintype "passive"))
    )
    (net (code "110") (name "unconnected-(HDR3-E28-Pad3)") (class "Default")
      (node (ref "HDR3") (pin "3") (pinfunction "E28_3") (pintype "passive"))
    )
    (net (code "111") (name "unconnected-(HDR3-JTAG-Pad4)") (class "Default")
      (node (ref "HDR3") (pin "4") (pinfunction "JTAG_4") (pintype "passive"))
    )
    (net (code "112") (name "unconnected-(HDR3-JTAG-Pad5)") (class "Default")
      (node (ref "HDR3") (pin "5") (pinfunction "JTAG_5") (pintype "passive"))
    )
    (net (code "113") (name "unconnected-(HDR3-JTAG-Pad6)") (class "Default")
      (node (ref "HDR3") (pin "6") (pinfunction "JTAG_6") (pintype "passive"))
    )
    (net (code "114") (name "unconnected-(HDR3-JTAG-Pad7)") (class "Default")
      (node (ref "HDR3") (pin "7") (pinfunction "JTAG_7") (pintype "passive"))
    )
    (net (code "115") (name "unconnected-(HDR3-JTAG-Pad8)") (class "Default")
      (node (ref "HDR3") (pin "8") (pinfunction "JTAG_8") (pintype "passive"))
    )
    (net (code "116") (name "unconnected-(HDR3-JTAG-Pad20)") (class "Default")
      (node (ref "HDR3") (pin "20") (pinfunction "JTAG_20") (pintype "passive"))
    )
    (net (code "117") (name "unconnected-(HDR3-JTAG-Pad21)") (class "Default")
      (node (ref "HDR3") (pin "21") (pinfunction "JTAG_21") (pintype "passive"))
    )
    (net (code "118") (name "unconnected-(HDR3-JTAG-Pad22)") (class "Default")
      (node (ref "HDR3") (pin "22") (pinfunction "JTAG_22") (pintype "passive"))
    )
    (net (code "119") (name "unconnected-(HDR4-0M1-Pad24)") (class "Default")
      (node (ref "HDR4") (pin "24") (pinfunction "0M1_24") (pintype "passive"))
    )
    (net (code "120") (name "unconnected-(HDR4-0M3-Pad27)") (class "Default")
      (node (ref "HDR4") (pin "27") (pinfunction "0M3_27") (pintype "passive"))
    )
    (net (code "121") (name "unconnected-(HDR4-0P1-Pad9)") (class "Default")
      (node (ref "HDR4") (pin "9") (pinfunction "0P1_9") (pintype "passive"))
    )
    (net (code "122") (name "unconnected-(HDR4-0P3-Pad12)") (class "Default")
      (node (ref "HDR4") (pin "12") (pinfunction "0P3_12") (pintype "passive"))
    )
    (net (code "123") (name "unconnected-(HDR4-0S16-Pad14)") (class "Default")
      (node (ref "HDR4") (pin "14") (pinfunction "0S16_14") (pintype "passive"))
    )
    (net (code "124") (name "unconnected-(HDR4-1M1-Pad25)") (class "Default")
      (node (ref "HDR4") (pin "25") (pinfunction "1M1_25") (pintype "passive"))
    )
    (net (code "125") (name "unconnected-(HDR4-1M3-Pad26)") (class "Default")
      (node (ref "HDR4") (pin "26") (pinfunction "1M3_26") (pintype "passive"))
    )
    (net (code "126") (name "unconnected-(HDR4-1P1-Pad10)") (class "Default")
      (node (ref "HDR4") (pin "10") (pinfunction "1P1_10") (pintype "passive"))
    )
    (net (code "127") (name "unconnected-(HDR4-1P3-Pad11)") (class "Default")
      (node (ref "HDR4") (pin "11") (pinfunction "1P3_11") (pintype "passive"))
    )
    (net (code "128") (name "unconnected-(HDR4-1S16-Pad28)") (class "Default")
      (node (ref "HDR4") (pin "28") (pinfunction "1S16_28") (pintype "passive"))
    )
    (net (code "129") (name "unconnected-(HDR4-1S18-Pad29)") (class "Default")
      (node (ref "HDR4") (pin "29") (pinfunction "1S18_29") (pintype "passive"))
    )
    (net (code "130") (name "unconnected-(HDR4-DA0-Pad15)") (class "Default")
      (node (ref "HDR4") (pin "15") (pinfunction "DA0_15") (pintype "passive"))
    )
    (net (code "131") (name "unconnected-(HDR4-DA1-Pad30)") (class "Default")
      (node (ref "HDR4") (pin "30") (pinfunction "DA1_30") (pintype "passive"))
    )
    (net (code "132") (name "unconnected-(HDR4-DM-Pad8)") (class "Default")
      (node (ref "HDR4") (pin "8") (pinfunction "DM_8") (pintype "passive"))
    )
    (net (code "133") (name "unconnected-(HDR4-DP-Pad22)") (class "Default")
      (node (ref "HDR4") (pin "22") (pinfunction "DP_22") (pintype "passive"))
    )
    (net (code "134") (name "unconnected-(HDR4-E9-Pad20)") (class "Default")
      (node (ref "HDR4") (pin "20") (pinfunction "E9_20") (pintype "passive"))
    )
    (net (code "135") (name "unconnected-(HDR4-E10-Pad6)") (class "Default")
      (node (ref "HDR4") (pin "6") (pinfunction "E10_6") (pintype "passive"))
    )
    (net (code "136") (name "unconnected-(HDR4-E11-Pad21)") (class "Default")
      (node (ref "HDR4") (pin "21") (pinfunction "E11_21") (pintype "passive"))
    )
    (net (code "137") (name "unconnected-(HDR4-E12-Pad7)") (class "Default")
      (node (ref "HDR4") (pin "7") (pinfunction "E12_7") (pintype "passive"))
    )
    (net (code "138") (name "unconnected-(HDR4-VRH-Pad13)") (class "Default")
      (node (ref "HDR4") (pin "13") (pinfunction "VRH_13") (pintype "passive"))
    )
    (net (code "139") (name "unconnected-(HDR4-VRIN-Pad23)") (class "Default")
      (node (ref "HDR4") (pin "23") (pinfunction "VRIN_23") (pintype "passive"))
    )
    (net (code "140") (name "unconnected-(J2-Pad5)") (class "Default")
      (node (ref "J2") (pin "5") (pinfunction "5_5") (pintype "passive+no_connect"))
    )
    (net (code "141") (name "unconnected-(J2-Pad6)") (class "Default")
      (node (ref "J2") (pin "6") (pinfunction "6_6") (pintype "passive+no_connect"))
    )
    (net (code "142") (name "unconnected-(J3-Pad5)") (class "Default")
      (node (ref "J3") (pin "5") (pinfunction "5_5") (pintype "passive+no_connect"))
    )
    (net (code "143") (name "unconnected-(J3-Pad6)") (class "Default")
      (node (ref "J3") (pin "6") (pinfunction "6_6") (pintype "passive+no_connect"))
    )
    (net (code "144") (name "unconnected-(P5-Pad1)") (class "Default")
      (node (ref "P5") (pin "1") (pinfunction "1_1") (pintype "passive"))
    )
    (net (code "145") (name "unconnected-(P5-Pad6)") (class "Default")
      (node (ref "P5") (pin "6") (pinfunction "6_6") (pintype "passive"))
    )
    (net (code "146") (name "unconnected-(P6-Pad1)") (class "Default")
      (node (ref "P6") (pin "1") (pinfunction "1_1") (pintype "passive"))
    )
    (net (code "147") (name "unconnected-(P6-Pad6)") (class "Default")
      (node (ref "P6") (pin "6") (pinfunction "6_6") (pintype "passive"))
    )
    (net (code "148") (name "unconnected-(S1-Pad1)") (class "Default")
      (node (ref "S1") (pin "1") (pinfunction "1_1") (pintype "passive"))
    )
    (net (code "149") (name "unconnected-(U3-FOOD-Pad13)") (class "Default")
      (node (ref "U3") (pin "13") (pinfunction "FOOD_13") (pintype "passive"))
    )
    (net (code "150") (name "unconnected-(U3-RES-Pad5)") (class "Default")
      (node (ref "U3") (pin "5") (pinfunction "RES_5") (pintype "passive"))
    )
    (net (code "151") (name "unconnected-(U3-SCL-Pad11)") (class "Default")
      (node (ref "U3") (pin "11") (pinfunction "SCL_11") (pintype "passive"))
    )
    (net (code "152") (name "unconnected-(U3-SDA-Pad2)") (class "Default")
      (node (ref "U3") (pin "2") (pinfunction "SDA_2") (pintype "passive"))
    )
    (net (code "153") (name "unconnected-(U3-VY0-Pad14)") (class "Default")
      (node (ref "U3") (pin "14") (pinfunction "VY0_14") (pintype "passive"))
    )
  )
)
